# contactor_single.net
KiCad netlist of a schematic drawn in Altium Designer
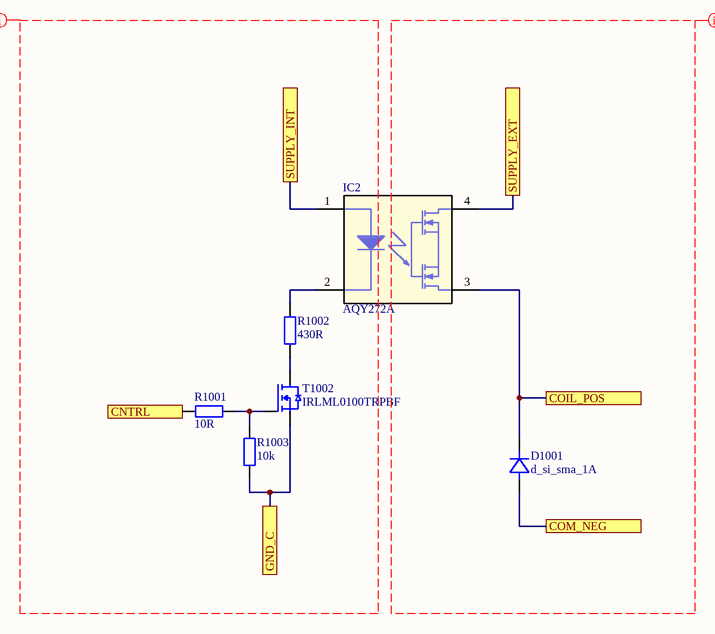
[diagram p0: contactor_single.SchDoc]

(export (version "E")
  (design (tool "Eeschema 10.0.6"))
  (components
    (comp (ref "D1001")
      (value "d_si_sma_1A")
      (footprint "DIOM4326X24N")
      (description "Standard Recovery Diode, 100 V, 1 A, Single, 1 V, 2 µs, 30 A")
      (fields (field (name "MANUFACTURER") "ON Semiconductor"))
      (libsource (lib "OE750") (part "D"))
    )
    (comp (ref "IC2")
      (value "AQY272A")
      (footprint "AQY27_PDIP_SMD")
      (fields (field (name "PARTNUMBER") "AQY212GHA") (field (name "MANUFACTURER") "Panasonic"))
      (libsource (lib "master-010106") (part "AQY272A"))
    )
    (comp (ref "R1001")
      (value "10R")
      (footprint "0603R")
      (description "SMD Resistor 10R 0603")
      (fields (field (name "PART NUMBER") "gen_R_10R_0603") (field (name "TOLERANCE") "1%"))
      (libsource (lib "master-010106") (part "R"))
    )
    (comp (ref "R1002")
      (value "430R")
      (footprint "0603R")
      (description "SMD Resistor 430R 0603")
      (fields (field (name "PART NUMBER") "gen_R_430R_0603") (field (name "TOLERANCE") "1%"))
      (libsource (lib "master-010106") (part "R"))
    )
    (comp (ref "R1003")
      (value "10k")
      (footprint "0603R")
      (description "SMD Resistor 10k 0603")
      (fields (field (name "PART NUMBER") "gen_R_10k_0603") (field (name "TOLERANCE") "1%"))
      (libsource (lib "master-010106") (part "R"))
    )
    (comp (ref "T1002")
      (value "IRLML0100TRPBF")
      (footprint "SOT95P237X110-3N")
      (description "MOSFET-Transistor, n-Kanal, 1.6 A, 100 V, 0.178 ohm, 10 V, 2.5 V")
      (fields (field (name "MANUFACTURER") "Infineon"))
      (libsource (lib "OE750") (part "NMOS"))
    )
  )
  (nets
    (net (code "1") (name "/CNTRL") (class "Default")
      (node (ref "R1001") (pin "2") (pinfunction "2_2") (pintype "passive"))
    )
    (net (code "2") (name "/COIL_POS") (class "Default")
      (node (ref "D1001") (pin "1") (pinfunction "K_1") (pintype "passive"))
      (node (ref "IC2") (pin "3") (pinfunction "3_3") (pintype "passive"))
    )
    (net (code "3") (name "/COM_NEG") (class "Default")
      (node (ref "D1001") (pin "2") (pinfunction "A_2") (pintype "passive"))
    )
    (net (code "4") (name "/GND_C") (class "Default")
      (node (ref "R1003") (pin "1") (pinfunction "1_1") (pintype "passive"))
      (node (ref "T1002") (pin "S") (pinfunction "S_S") (pintype "passive"))
    )
    (net (code "5") (name "/SUPPLY_EXT") (class "Default")
      (node (ref "IC2") (pin "4") (pinfunction "4_4") (pintype "passive"))
    )
    (net (code "6") (name "/SUPPLY_INT") (class "Default")
      (node (ref "IC2") (pin "1") (pinfunction "1_1") (pintype "passive"))
    )
    (net (code "7") (name "Net-(IC2-Pad2)") (class "Default")
      (node (ref "IC2") (pin "2") (pinfunction "2_2") (pintype "passive"))
      (node (ref "R1002") (pin "2") (pinfunction "2_2") (pintype "passive"))
    )
    (net (code "8") (name "Net-(R1001-Pad1)") (class "Default")
      (node (ref "R1001") (pin "1") (pinfunction "1_1") (pintype "passive"))
      (node (ref "R1003") (pin "2") (pinfunction "2_2") (pintype "passive"))
      (node (ref "T1002") (pin "G") (pinfunction "G_G") (pintype "passive"))
    )
    (net (code "9") (name "Net-(R1002-Pad1)") (class "Default")
      (node (ref "R1002") (pin "1") (pinfunction "1_1") (pintype "passive"))
      (node (ref "T1002") (pin "D") (pinfunction "D_D") (pintype "passive"))
    )
  )
)
